# W520X.net
KiCad netlist of a schematic drawn in EAGLE
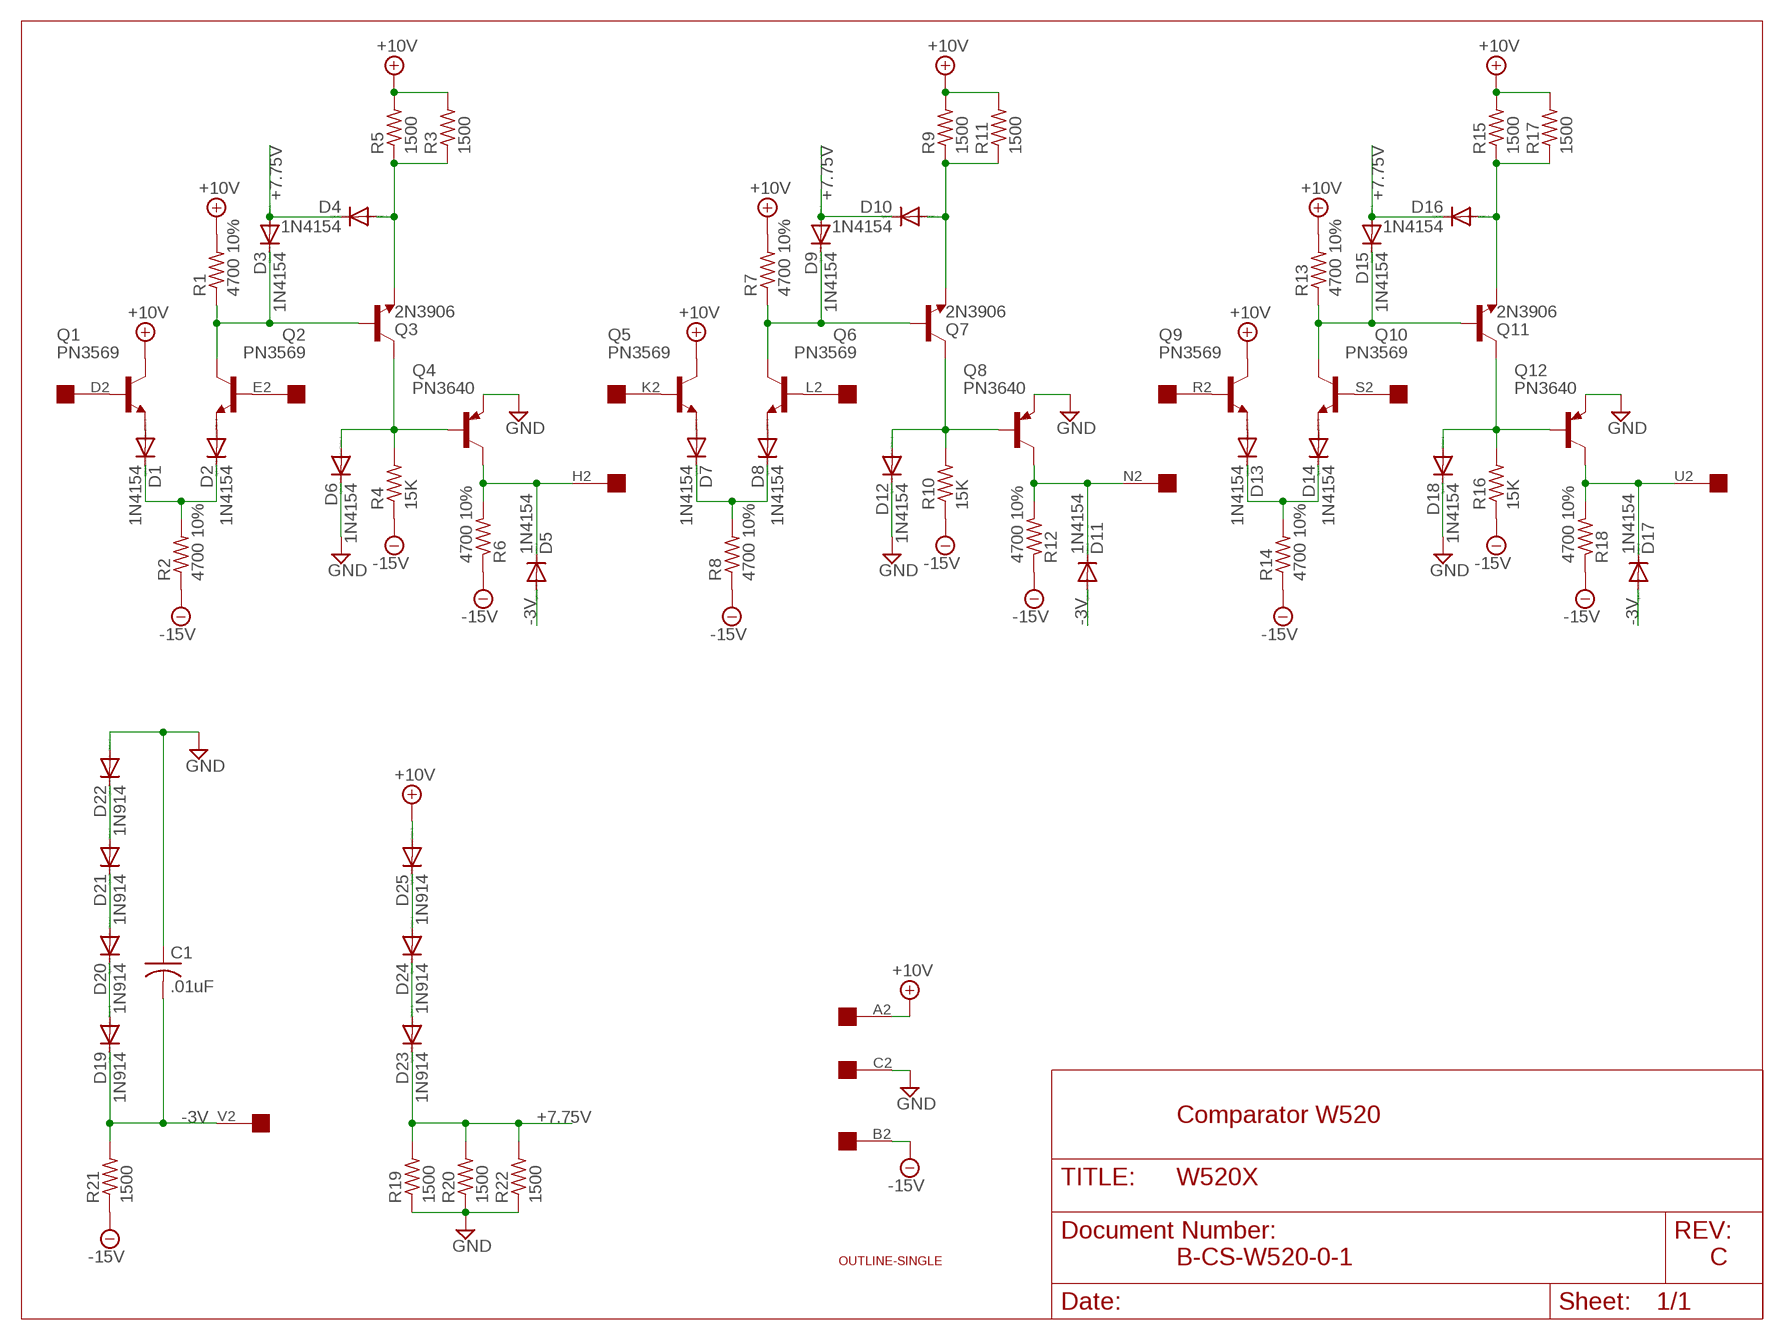
[diagram p0: schematic, sheet 1]

(export (version "E")
  (design (tool "Eeschema 10.0.6"))
  (components
    (comp (ref "C1")
      (value ".01uF")
      (footprint "eagle-import:C150-054X183")
      (libsource (lib "eagle-import") (part "C-US150-054X183"))
    )
    (comp (ref "D1")
      (value "1N4154")
      (footprint "eagle-import:DO35-10")
      (libsource (lib "eagle-import") (part "1N4148DO35-10"))
    )
    (comp (ref "D2")
      (value "1N4154")
      (footprint "eagle-import:DO35-10")
      (libsource (lib "eagle-import") (part "1N4148DO35-10"))
    )
    (comp (ref "D3")
      (value "1N4154")
      (footprint "eagle-import:DO35-10")
      (libsource (lib "eagle-import") (part "1N4148DO35-10"))
    )
    (comp (ref "D4")
      (value "1N4154")
      (footprint "eagle-import:DO35-10")
      (libsource (lib "eagle-import") (part "1N4148DO35-10"))
    )
    (comp (ref "D5")
      (value "1N4154")
      (footprint "eagle-import:DO35-10")
      (libsource (lib "eagle-import") (part "1N4148DO35-10"))
    )
    (comp (ref "D6")
      (value "1N4154")
      (footprint "eagle-import:DO35-10")
      (libsource (lib "eagle-import") (part "1N4148DO35-10"))
    )
    (comp (ref "D7")
      (value "1N4154")
      (footprint "eagle-import:DO35-10")
      (libsource (lib "eagle-import") (part "1N4148DO35-10"))
    )
    (comp (ref "D8")
      (value "1N4154")
      (footprint "eagle-import:DO35-10")
      (libsource (lib "eagle-import") (part "1N4148DO35-10"))
    )
    (comp (ref "D9")
      (value "1N4154")
      (footprint "eagle-import:DO35-10")
      (libsource (lib "eagle-import") (part "1N4148DO35-10"))
    )
    (comp (ref "D10")
      (value "1N4154")
      (footprint "eagle-import:DO35-10")
      (libsource (lib "eagle-import") (part "1N4148DO35-10"))
    )
    (comp (ref "D11")
      (value "1N4154")
      (footprint "eagle-import:DO35-10")
      (libsource (lib "eagle-import") (part "1N4148DO35-10"))
    )
    (comp (ref "D12")
      (value "1N4154")
      (footprint "eagle-import:DO35-10")
      (libsource (lib "eagle-import") (part "1N4148DO35-10"))
    )
    (comp (ref "D13")
      (value "1N4154")
      (footprint "eagle-import:DO35-10")
      (libsource (lib "eagle-import") (part "1N4148DO35-10"))
    )
    (comp (ref "D14")
      (value "1N4154")
      (footprint "eagle-import:DO35-10")
      (libsource (lib "eagle-import") (part "1N4148DO35-10"))
    )
    (comp (ref "D15")
      (value "1N4154")
      (footprint "eagle-import:DO35-10")
      (libsource (lib "eagle-import") (part "1N4148DO35-10"))
    )
    (comp (ref "D16")
      (value "1N4154")
      (footprint "eagle-import:DO35-10")
      (libsource (lib "eagle-import") (part "1N4148DO35-10"))
    )
    (comp (ref "D17")
      (value "1N4154")
      (footprint "eagle-import:DO35-10")
      (libsource (lib "eagle-import") (part "1N4148DO35-10"))
    )
    (comp (ref "D18")
      (value "1N4154")
      (footprint "eagle-import:DO35-10")
      (libsource (lib "eagle-import") (part "1N4148DO35-10"))
    )
    (comp (ref "D19")
      (value "1N914")
      (footprint "eagle-import:DO35-10")
      (libsource (lib "eagle-import") (part "1N4148DO35-10"))
    )
    (comp (ref "D20")
      (value "1N914")
      (footprint "eagle-import:DO35-10")
      (libsource (lib "eagle-import") (part "1N4148DO35-10"))
    )
    (comp (ref "D21")
      (value "1N914")
      (footprint "eagle-import:DO35-10")
      (libsource (lib "eagle-import") (part "1N4148DO35-10"))
    )
    (comp (ref "D22")
      (value "1N914")
      (footprint "eagle-import:DO35-10")
      (libsource (lib "eagle-import") (part "1N4148DO35-10"))
    )
    (comp (ref "D23")
      (value "1N914")
      (footprint "eagle-import:DO35-10")
      (libsource (lib "eagle-import") (part "1N4148DO35-10"))
    )
    (comp (ref "D24")
      (value "1N914")
      (footprint "eagle-import:DO35-10")
      (libsource (lib "eagle-import") (part "1N4148DO35-10"))
    )
    (comp (ref "D25")
      (value "1N914")
      (footprint "eagle-import:DO35-10")
      (libsource (lib "eagle-import") (part "1N4148DO35-10"))
    )
    (comp (ref "Q1")
      (value "PN3569")
      (footprint "eagle-import:TO5")
      (libsource (lib "eagle-import") (part "2N2102"))
    )
    (comp (ref "Q2")
      (value "PN3569")
      (footprint "eagle-import:TO5")
      (libsource (lib "eagle-import") (part "2N2102"))
    )
    (comp (ref "Q3")
      (value "2N3906")
      (footprint "eagle-import:TO5")
      (libsource (lib "eagle-import") (part "2N2102"))
    )
    (comp (ref "Q4")
      (value "PN3640")
      (footprint "eagle-import:TO39")
      (libsource (lib "eagle-import") (part "2N2904"))
    )
    (comp (ref "Q5")
      (value "PN3569")
      (footprint "eagle-import:TO5")
      (libsource (lib "eagle-import") (part "2N2102"))
    )
    (comp (ref "Q6")
      (value "PN3569")
      (footprint "eagle-import:TO5")
      (libsource (lib "eagle-import") (part "2N2102"))
    )
    (comp (ref "Q7")
      (value "2N3906")
      (footprint "eagle-import:TO5")
      (libsource (lib "eagle-import") (part "2N2102"))
    )
    (comp (ref "Q8")
      (value "PN3640")
      (footprint "eagle-import:TO39")
      (libsource (lib "eagle-import") (part "2N2904"))
    )
    (comp (ref "Q9")
      (value "PN3569")
      (footprint "eagle-import:TO5")
      (libsource (lib "eagle-import") (part "2N2102"))
    )
    (comp (ref "Q10")
      (value "PN3569")
      (footprint "eagle-import:TO5")
      (libsource (lib "eagle-import") (part "2N2102"))
    )
    (comp (ref "Q11")
      (value "2N3906")
      (footprint "eagle-import:TO5")
      (libsource (lib "eagle-import") (part "2N2102"))
    )
    (comp (ref "Q12")
      (value "PN3640")
      (footprint "eagle-import:TO39")
      (libsource (lib "eagle-import") (part "2N2904"))
    )
    (comp (ref "R1")
      (value "4700 10%")
      (footprint "eagle-import:0207_10")
      (libsource (lib "eagle-import") (part "R-US_0207/10"))
    )
    (comp (ref "R2")
      (value "4700 10%")
      (footprint "eagle-import:0207_10")
      (libsource (lib "eagle-import") (part "R-US_0207/10"))
    )
    (comp (ref "R3")
      (value "1500")
      (footprint "eagle-import:0207_10")
      (libsource (lib "eagle-import") (part "R-US_0207/10"))
    )
    (comp (ref "R4")
      (value "15K")
      (footprint "eagle-import:0207_10")
      (libsource (lib "eagle-import") (part "R-US_0207/10"))
    )
    (comp (ref "R5")
      (value "1500")
      (footprint "eagle-import:0207_10")
      (libsource (lib "eagle-import") (part "R-US_0207/10"))
    )
    (comp (ref "R6")
      (value "4700 10%")
      (footprint "eagle-import:0207_10")
      (libsource (lib "eagle-import") (part "R-US_0207/10"))
    )
    (comp (ref "R7")
      (value "4700 10%")
      (footprint "eagle-import:0207_10")
      (libsource (lib "eagle-import") (part "R-US_0207/10"))
    )
    (comp (ref "R8")
      (value "4700 10%")
      (footprint "eagle-import:0207_10")
      (libsource (lib "eagle-import") (part "R-US_0207/10"))
    )
    (comp (ref "R9")
      (value "1500")
      (footprint "eagle-import:0207_10")
      (libsource (lib "eagle-import") (part "R-US_0207/10"))
    )
    (comp (ref "R10")
      (value "15K")
      (footprint "eagle-import:0207_10")
      (libsource (lib "eagle-import") (part "R-US_0207/10"))
    )
    (comp (ref "R11")
      (value "1500")
      (footprint "eagle-import:0207_10")
      (libsource (lib "eagle-import") (part "R-US_0207/10"))
    )
    (comp (ref "R12")
      (value "4700 10%")
      (footprint "eagle-import:0207_10")
      (libsource (lib "eagle-import") (part "R-US_0207/10"))
    )
    (comp (ref "R13")
      (value "4700 10%")
      (footprint "eagle-import:0207_10")
      (libsource (lib "eagle-import") (part "R-US_0207/10"))
    )
    (comp (ref "R14")
      (value "4700 10%")
      (footprint "eagle-import:0207_10")
      (libsource (lib "eagle-import") (part "R-US_0207/10"))
    )
    (comp (ref "R15")
      (value "1500")
      (footprint "eagle-import:0207_10")
      (libsource (lib "eagle-import") (part "R-US_0207/10"))
    )
    (comp (ref "R16")
      (value "15K")
      (footprint "eagle-import:0207_10")
      (libsource (lib "eagle-import") (part "R-US_0207/10"))
    )
    (comp (ref "R17")
      (value "1500")
      (footprint "eagle-import:0207_10")
      (libsource (lib "eagle-import") (part "R-US_0207/10"))
    )
    (comp (ref "R18")
      (value "4700 10%")
      (footprint "eagle-import:0207_10")
      (libsource (lib "eagle-import") (part "R-US_0207/10"))
    )
    (comp (ref "R19")
      (value "1500")
      (footprint "eagle-import:0207_10")
      (libsource (lib "eagle-import") (part "R-US_0207/10"))
    )
    (comp (ref "R20")
      (value "1500")
      (footprint "eagle-import:0207_10")
      (libsource (lib "eagle-import") (part "R-US_0207/10"))
    )
    (comp (ref "R21")
      (value "1500")
      (footprint "eagle-import:0207_10")
      (libsource (lib "eagle-import") (part "R-US_0207/10"))
    )
    (comp (ref "R22")
      (value "1500")
      (footprint "eagle-import:0207_10")
      (libsource (lib "eagle-import") (part "R-US_0207/10"))
    )
    (comp (ref "U$1")
      (value "OUTLINE-SINGLE")
      (footprint "eagle-import:SINGLE")
      (libsource (lib "eagle-import") (part "OUTLINE-SINGLE"))
    )
    (comp (ref "U$2")
      (value "EDGE-1")
      (footprint "eagle-import:EDGE-CON1")
      (libsource (lib "eagle-import") (part "EDGE-1"))
    )
  )
  (nets
    (net (code "1") (name "+10V") (class "Default")
      (node (ref "D25") (pin "A") (pinfunction "A_A") (pintype "passive"))
      (node (ref "Q1") (pin "3") (pinfunction "C_3") (pintype "passive"))
      (node (ref "Q5") (pin "3") (pinfunction "C_3") (pintype "passive"))
      (node (ref "Q9") (pin "3") (pinfunction "C_3") (pintype "passive"))
      (node (ref "R1") (pin "2") (pinfunction "2_2") (pintype "passive"))
      (node (ref "R11") (pin "2") (pinfunction "2_2") (pintype "passive"))
      (node (ref "R13") (pin "2") (pinfunction "2_2") (pintype "passive"))
      (node (ref "R15") (pin "2") (pinfunction "2_2") (pintype "passive"))
      (node (ref "R17") (pin "2") (pinfunction "2_2") (pintype "passive"))
      (node (ref "R3") (pin "2") (pinfunction "2_2") (pintype "passive"))
      (node (ref "R5") (pin "2") (pinfunction "2_2") (pintype "passive"))
      (node (ref "R7") (pin "2") (pinfunction "2_2") (pintype "passive"))
      (node (ref "R9") (pin "2") (pinfunction "2_2") (pintype "passive"))
      (node (ref "U$2") (pin "A2") (pinfunction "1_A2") (pintype "bidirectional"))
    )
    (net (code "2") (name "-15V") (class "Default")
      (node (ref "R10") (pin "1") (pinfunction "1_1") (pintype "passive"))
      (node (ref "R12") (pin "1") (pinfunction "1_1") (pintype "passive"))
      (node (ref "R14") (pin "1") (pinfunction "1_1") (pintype "passive"))
      (node (ref "R16") (pin "1") (pinfunction "1_1") (pintype "passive"))
      (node (ref "R18") (pin "1") (pinfunction "1_1") (pintype "passive"))
      (node (ref "R2") (pin "1") (pinfunction "1_1") (pintype "passive"))
      (node (ref "R21") (pin "1") (pinfunction "1_1") (pintype "passive"))
      (node (ref "R4") (pin "1") (pinfunction "1_1") (pintype "passive"))
      (node (ref "R6") (pin "1") (pinfunction "1_1") (pintype "passive"))
      (node (ref "R8") (pin "1") (pinfunction "1_1") (pintype "passive"))
      (node (ref "U$2") (pin "B2") (pinfunction "1_B2") (pintype "bidirectional"))
    )
    (net (code "3") (name "/+7.75V") (class "Default")
      (node (ref "D10") (pin "C") (pinfunction "C_C") (pintype "passive"))
      (node (ref "D15") (pin "A") (pinfunction "A_A") (pintype "passive"))
      (node (ref "D16") (pin "C") (pinfunction "C_C") (pintype "passive"))
      (node (ref "D23") (pin "C") (pinfunction "C_C") (pintype "passive"))
      (node (ref "D3") (pin "A") (pinfunction "A_A") (pintype "passive"))
      (node (ref "D4") (pin "C") (pinfunction "C_C") (pintype "passive"))
      (node (ref "D9") (pin "A") (pinfunction "A_A") (pintype "passive"))
      (node (ref "R19") (pin "2") (pinfunction "2_2") (pintype "passive"))
      (node (ref "R20") (pin "2") (pinfunction "2_2") (pintype "passive"))
      (node (ref "R22") (pin "2") (pinfunction "2_2") (pintype "passive"))
    )
    (net (code "4") (name "/-3V") (class "Default")
      (node (ref "C1") (pin "2") (pinfunction "2_2") (pintype "passive"))
      (node (ref "D11") (pin "A") (pinfunction "A_A") (pintype "passive"))
      (node (ref "D17") (pin "A") (pinfunction "A_A") (pintype "passive"))
      (node (ref "D19") (pin "C") (pinfunction "C_C") (pintype "passive"))
      (node (ref "D5") (pin "A") (pinfunction "A_A") (pintype "passive"))
      (node (ref "R21") (pin "2") (pinfunction "2_2") (pintype "passive"))
      (node (ref "U$2") (pin "V2") (pinfunction "1_V2") (pintype "bidirectional"))
    )
    (net (code "5") (name "GND") (class "Default")
      (node (ref "C1") (pin "1") (pinfunction "1_1") (pintype "passive"))
      (node (ref "D12") (pin "C") (pinfunction "C_C") (pintype "passive"))
      (node (ref "D18") (pin "C") (pinfunction "C_C") (pintype "passive"))
      (node (ref "D22") (pin "A") (pinfunction "A_A") (pintype "passive"))
      (node (ref "D6") (pin "C") (pinfunction "C_C") (pintype "passive"))
      (node (ref "Q12") (pin "1") (pinfunction "E_1") (pintype "passive"))
      (node (ref "Q4") (pin "1") (pinfunction "E_1") (pintype "passive"))
      (node (ref "Q8") (pin "1") (pinfunction "E_1") (pintype "passive"))
      (node (ref "R19") (pin "1") (pinfunction "1_1") (pintype "passive"))
      (node (ref "R20") (pin "1") (pinfunction "1_1") (pintype "passive"))
      (node (ref "R22") (pin "1") (pinfunction "1_1") (pintype "passive"))
      (node (ref "U$2") (pin "C2") (pinfunction "1_C2") (pintype "bidirectional"))
    )
    (net (code "6") (name "Net-(D1-PadC)") (class "Default")
      (node (ref "D1") (pin "C") (pinfunction "C_C") (pintype "passive"))
      (node (ref "D2") (pin "C") (pinfunction "C_C") (pintype "passive"))
      (node (ref "R2") (pin "2") (pinfunction "2_2") (pintype "passive"))
    )
    (net (code "7") (name "Net-(D7-PadC)") (class "Default")
      (node (ref "D7") (pin "C") (pinfunction "C_C") (pintype "passive"))
      (node (ref "D8") (pin "C") (pinfunction "C_C") (pintype "passive"))
      (node (ref "R8") (pin "2") (pinfunction "2_2") (pintype "passive"))
    )
    (net (code "8") (name "Net-(D13-PadC)") (class "Default")
      (node (ref "D13") (pin "C") (pinfunction "C_C") (pintype "passive"))
      (node (ref "D14") (pin "C") (pinfunction "C_C") (pintype "passive"))
      (node (ref "R14") (pin "2") (pinfunction "2_2") (pintype "passive"))
    )
    (net (code "9") (name "Net-(D19-PadA)") (class "Default")
      (node (ref "D19") (pin "A") (pinfunction "A_A") (pintype "passive"))
      (node (ref "D20") (pin "C") (pinfunction "C_C") (pintype "passive"))
    )
    (net (code "10") (name "Net-(D20-PadA)") (class "Default")
      (node (ref "D20") (pin "A") (pinfunction "A_A") (pintype "passive"))
      (node (ref "D21") (pin "C") (pinfunction "C_C") (pintype "passive"))
    )
    (net (code "11") (name "Net-(D21-PadA)") (class "Default")
      (node (ref "D21") (pin "A") (pinfunction "A_A") (pintype "passive"))
      (node (ref "D22") (pin "C") (pinfunction "C_C") (pintype "passive"))
    )
    (net (code "12") (name "Net-(D23-PadA)") (class "Default")
      (node (ref "D23") (pin "A") (pinfunction "A_A") (pintype "passive"))
      (node (ref "D24") (pin "C") (pinfunction "C_C") (pintype "passive"))
    )
    (net (code "13") (name "Net-(D24-PadA)") (class "Default")
      (node (ref "D24") (pin "A") (pinfunction "A_A") (pintype "passive"))
      (node (ref "D25") (pin "C") (pinfunction "C_C") (pintype "passive"))
    )
    (net (code "14") (name "Net-(Q1-B)") (class "Default")
      (node (ref "Q1") (pin "2") (pinfunction "B_2") (pintype "passive"))
      (node (ref "U$2") (pin "D2") (pinfunction "1_D2") (pintype "bidirectional"))
    )
    (net (code "15") (name "Net-(Q1-E)") (class "Default")
      (node (ref "D1") (pin "A") (pinfunction "A_A") (pintype "passive"))
      (node (ref "Q1") (pin "1") (pinfunction "E_1") (pintype "passive"))
    )
    (net (code "16") (name "Net-(Q2-B)") (class "Default")
      (node (ref "Q2") (pin "2") (pinfunction "B_2") (pintype "passive"))
      (node (ref "U$2") (pin "E2") (pinfunction "1_E2") (pintype "bidirectional"))
    )
    (net (code "17") (name "Net-(Q2-C)") (class "Default")
      (node (ref "D3") (pin "C") (pinfunction "C_C") (pintype "passive"))
      (node (ref "Q2") (pin "3") (pinfunction "C_3") (pintype "passive"))
      (node (ref "Q3") (pin "2") (pinfunction "B_2") (pintype "passive"))
      (node (ref "R1") (pin "1") (pinfunction "1_1") (pintype "passive"))
    )
    (net (code "18") (name "Net-(Q2-E)") (class "Default")
      (node (ref "D2") (pin "A") (pinfunction "A_A") (pintype "passive"))
      (node (ref "Q2") (pin "1") (pinfunction "E_1") (pintype "passive"))
    )
    (net (code "19") (name "Net-(Q3-C)") (class "Default")
      (node (ref "D6") (pin "A") (pinfunction "A_A") (pintype "passive"))
      (node (ref "Q3") (pin "3") (pinfunction "C_3") (pintype "passive"))
      (node (ref "Q4") (pin "2") (pinfunction "B_2") (pintype "passive"))
      (node (ref "R4") (pin "2") (pinfunction "2_2") (pintype "passive"))
    )
    (net (code "20") (name "Net-(Q3-E)") (class "Default")
      (node (ref "D4") (pin "A") (pinfunction "A_A") (pintype "passive"))
      (node (ref "Q3") (pin "1") (pinfunction "E_1") (pintype "passive"))
      (node (ref "R3") (pin "1") (pinfunction "1_1") (pintype "passive"))
      (node (ref "R5") (pin "1") (pinfunction "1_1") (pintype "passive"))
    )
    (net (code "21") (name "Net-(Q4-C)") (class "Default")
      (node (ref "D5") (pin "C") (pinfunction "C_C") (pintype "passive"))
      (node (ref "Q4") (pin "3") (pinfunction "C_3") (pintype "passive"))
      (node (ref "R6") (pin "2") (pinfunction "2_2") (pintype "passive"))
      (node (ref "U$2") (pin "H2") (pinfunction "1_H2") (pintype "bidirectional"))
    )
    (net (code "22") (name "Net-(Q5-B)") (class "Default")
      (node (ref "Q5") (pin "2") (pinfunction "B_2") (pintype "passive"))
      (node (ref "U$2") (pin "K2") (pinfunction "1_K2") (pintype "bidirectional"))
    )
    (net (code "23") (name "Net-(Q5-E)") (class "Default")
      (node (ref "D7") (pin "A") (pinfunction "A_A") (pintype "passive"))
      (node (ref "Q5") (pin "1") (pinfunction "E_1") (pintype "passive"))
    )
    (net (code "24") (name "Net-(Q6-B)") (class "Default")
      (node (ref "Q6") (pin "2") (pinfunction "B_2") (pintype "passive"))
      (node (ref "U$2") (pin "L2") (pinfunction "1_L2") (pintype "bidirectional"))
    )
    (net (code "25") (name "Net-(Q6-C)") (class "Default")
      (node (ref "D9") (pin "C") (pinfunction "C_C") (pintype "passive"))
      (node (ref "Q6") (pin "3") (pinfunction "C_3") (pintype "passive"))
      (node (ref "Q7") (pin "2") (pinfunction "B_2") (pintype "passive"))
      (node (ref "R7") (pin "1") (pinfunction "1_1") (pintype "passive"))
    )
    (net (code "26") (name "Net-(Q6-E)") (class "Default")
      (node (ref "D8") (pin "A") (pinfunction "A_A") (pintype "passive"))
      (node (ref "Q6") (pin "1") (pinfunction "E_1") (pintype "passive"))
    )
    (net (code "27") (name "Net-(Q7-C)") (class "Default")
      (node (ref "D12") (pin "A") (pinfunction "A_A") (pintype "passive"))
      (node (ref "Q7") (pin "3") (pinfunction "C_3") (pintype "passive"))
      (node (ref "Q8") (pin "2") (pinfunction "B_2") (pintype "passive"))
      (node (ref "R10") (pin "2") (pinfunction "2_2") (pintype "passive"))
    )
    (net (code "28") (name "Net-(Q7-E)") (class "Default")
      (node (ref "D10") (pin "A") (pinfunction "A_A") (pintype "passive"))
      (node (ref "Q7") (pin "1") (pinfunction "E_1") (pintype "passive"))
      (node (ref "R11") (pin "1") (pinfunction "1_1") (pintype "passive"))
      (node (ref "R9") (pin "1") (pinfunction "1_1") (pintype "passive"))
    )
    (net (code "29") (name "Net-(Q8-C)") (class "Default")
      (node (ref "D11") (pin "C") (pinfunction "C_C") (pintype "passive"))
      (node (ref "Q8") (pin "3") (pinfunction "C_3") (pintype "passive"))
      (node (ref "R12") (pin "2") (pinfunction "2_2") (pintype "passive"))
      (node (ref "U$2") (pin "N2") (pinfunction "1_N2") (pintype "bidirectional"))
    )
    (net (code "30") (name "Net-(Q9-B)") (class "Default")
      (node (ref "Q9") (pin "2") (pinfunction "B_2") (pintype "passive"))
      (node (ref "U$2") (pin "R2") (pinfunction "1_R2") (pintype "bidirectional"))
    )
    (net (code "31") (name "Net-(Q9-E)") (class "Default")
      (node (ref "D13") (pin "A") (pinfunction "A_A") (pintype "passive"))
      (node (ref "Q9") (pin "1") (pinfunction "E_1") (pintype "passive"))
    )
    (net (code "32") (name "Net-(Q10-B)") (class "Default")
      (node (ref "Q10") (pin "2") (pinfunction "B_2") (pintype "passive"))
      (node (ref "U$2") (pin "S2") (pinfunction "1_S2") (pintype "bidirectional"))
    )
    (net (code "33") (name "Net-(Q10-C)") (class "Default")
      (node (ref "D15") (pin "C") (pinfunction "C_C") (pintype "passive"))
      (node (ref "Q10") (pin "3") (pinfunction "C_3") (pintype "passive"))
      (node (ref "Q11") (pin "2") (pinfunction "B_2") (pintype "passive"))
      (node (ref "R13") (pin "1") (pinfunction "1_1") (pintype "passive"))
    )
    (net (code "34") (name "Net-(Q10-E)") (class "Default")
      (node (ref "D14") (pin "A") (pinfunction "A_A") (pintype "passive"))
      (node (ref "Q10") (pin "1") (pinfunction "E_1") (pintype "passive"))
    )
    (net (code "35") (name "Net-(Q11-C)") (class "Default")
      (node (ref "D18") (pin "A") (pinfunction "A_A") (pintype "passive"))
      (node (ref "Q11") (pin "3") (pinfunction "C_3") (pintype "passive"))
      (node (ref "Q12") (pin "2") (pinfunction "B_2") (pintype "passive"))
      (node (ref "R16") (pin "2") (pinfunction "2_2") (pintype "passive"))
    )
    (net (code "36") (name "Net-(Q11-E)") (class "Default")
      (node (ref "D16") (pin "A") (pinfunction "A_A") (pintype "passive"))
      (node (ref "Q11") (pin "1") (pinfunction "E_1") (pintype "passive"))
      (node (ref "R15") (pin "1") (pinfunction "1_1") (pintype "passive"))
      (node (ref "R17") (pin "1") (pinfunction "1_1") (pintype "passive"))
    )
    (net (code "37") (name "Net-(Q12-C)") (class "Default")
      (node (ref "D17") (pin "C") (pinfunction "C_C") (pintype "passive"))
      (node (ref "Q12") (pin "3") (pinfunction "C_3") (pintype "passive"))
      (node (ref "R18") (pin "2") (pinfunction "2_2") (pintype "passive"))
      (node (ref "U$2") (pin "U2") (pinfunction "1_U2") (pintype "bidirectional"))
    )
  )
)
